# BLE_Master.net
KiCad netlist of a schematic drawn in EAGLE
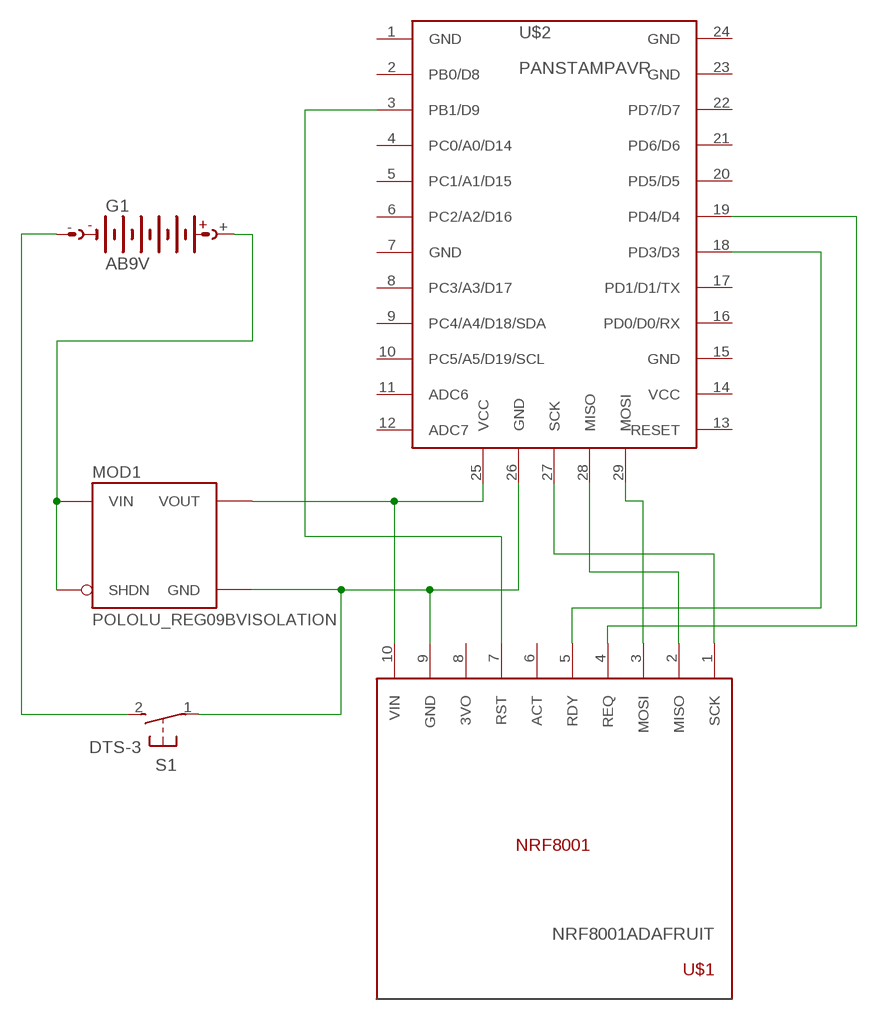
[diagram p0: schematic, sheet 1]

(export (version "E")
  (design (tool "Eeschema 10.0.6"))
  (components
    (comp (ref "G1")
      (value "AB9V")
      (footprint "eagle-import:AB9V")
      (libsource (lib "eagle-import") (part "AB9V"))
    )
    (comp (ref "MOD1")
      (value "POLOLU_REG09BVISOLATION")
      (footprint "eagle-import:POLOLU_REG09B_ISO")
      (libsource (lib "eagle-import") (part "POLOLU_REG09BVISOLATION"))
    )
    (comp (ref "S1")
      (value "DTS-3")
      (footprint "eagle-import:DTS-3")
      (libsource (lib "eagle-import") (part "DTS-3"))
    )
    (comp (ref "U$1")
      (value "NRF8001ADAFRUIT")
      (footprint "eagle-import:NRF8001_ADAFRUIT")
      (libsource (lib "eagle-import") (part "NRF8001ADAFRUIT"))
    )
    (comp (ref "U$2")
      (value "PANSTAMPAVR")
      (footprint "eagle-import:PANSTAMP")
      (libsource (lib "eagle-import") (part "PANSTAMPAVR"))
    )
  )
  (nets
    (net (code "1") (name "Net-(G1-Pad-)") (class "Default")
      (node (ref "G1") (pin "-") (pinfunction "-_-") (pintype "passive"))
      (node (ref "S1") (pin "2") (pinfunction "2_2") (pintype "passive"))
    )
    (net (code "2") (name "Net-(MOD1-GND)") (class "Default")
      (node (ref "MOD1") (pin "G") (pinfunction "GND_G") (pintype "power_in"))
      (node (ref "S1") (pin "1") (pinfunction "1_1") (pintype "passive"))
      (node (ref "U$1") (pin "9") (pinfunction "GND_9") (pintype "bidirectional"))
      (node (ref "U$2") (pin "26") (pinfunction "GND_26") (pintype "bidirectional"))
    )
    (net (code "3") (name "Net-(MOD1-SHDN)") (class "Default")
      (node (ref "G1") (pin "+") (pinfunction "+_+") (pintype "passive"))
      (node (ref "MOD1") (pin "I") (pinfunction "VIN_I") (pintype "power_in"))
      (node (ref "MOD1") (pin "S") (pinfunction "SHDN_S") (pintype "input"))
    )
    (net (code "4") (name "Net-(MOD1-VOUT)") (class "Default")
      (node (ref "MOD1") (pin "O") (pinfunction "VOUT_O") (pintype "output"))
      (node (ref "U$1") (pin "10") (pinfunction "VIN_10") (pintype "bidirectional"))
      (node (ref "U$2") (pin "25") (pinfunction "VCC_25") (pintype "bidirectional"))
    )
    (net (code "5") (name "Net-(U$1-MISO)") (class "Default")
      (node (ref "U$1") (pin "2") (pinfunction "MISO_2") (pintype "bidirectional"))
      (node (ref "U$2") (pin "28") (pinfunction "MISO_28") (pintype "bidirectional"))
    )
    (net (code "6") (name "Net-(U$1-MOSI)") (class "Default")
      (node (ref "U$1") (pin "3") (pinfunction "MOSI_3") (pintype "bidirectional"))
      (node (ref "U$2") (pin "29") (pinfunction "MOSI_29") (pintype "bidirectional"))
    )
    (net (code "7") (name "Net-(U$1-RDY)") (class "Default")
      (node (ref "U$1") (pin "5") (pinfunction "RDY_5") (pintype "bidirectional"))
      (node (ref "U$2") (pin "18") (pinfunction "PD3/D3_18") (pintype "bidirectional"))
    )
    (net (code "8") (name "Net-(U$1-REQ)") (class "Default")
      (node (ref "U$1") (pin "4") (pinfunction "REQ_4") (pintype "bidirectional"))
      (node (ref "U$2") (pin "19") (pinfunction "PD4/D4_19") (pintype "bidirectional"))
    )
    (net (code "9") (name "Net-(U$1-RST)") (class "Default")
      (node (ref "U$1") (pin "7") (pinfunction "RST_7") (pintype "bidirectional"))
      (node (ref "U$2") (pin "3") (pinfunction "PB1/D9_3") (pintype "bidirectional"))
    )
    (net (code "10") (name "Net-(U$1-SCK)") (class "Default")
      (node (ref "U$1") (pin "1") (pinfunction "SCK_1") (pintype "bidirectional"))
      (node (ref "U$2") (pin "27") (pinfunction "SCK_27") (pintype "bidirectional"))
    )
    (net (code "11") (name "unconnected-(U$1-3VO-Pad8)") (class "Default")
      (node (ref "U$1") (pin "8") (pinfunction "3VO_8") (pintype "bidirectional"))
    )
    (net (code "12") (name "unconnected-(U$1-ACT-Pad6)") (class "Default")
      (node (ref "U$1") (pin "6") (pinfunction "ACT_6") (pintype "bidirectional"))
    )
    (net (code "13") (name "unconnected-(U$2-ADC6-Pad11)") (class "Default")
      (node (ref "U$2") (pin "11") (pinfunction "ADC6_11") (pintype "bidirectional"))
    )
    (net (code "14") (name "unconnected-(U$2-ADC7-Pad12)") (class "Default")
      (node (ref "U$2") (pin "12") (pinfunction "ADC7_12") (pintype "bidirectional"))
    )
    (net (code "15") (name "unconnected-(U$2-GND-Pad1)") (class "Default")
      (node (ref "U$2") (pin "1") (pinfunction "GND_1") (pintype "bidirectional"))
    )
    (net (code "16") (name "unconnected-(U$2-GND-Pad7)") (class "Default")
      (node (ref "U$2") (pin "7") (pinfunction "GND_7") (pintype "bidirectional"))
    )
    (net (code "17") (name "unconnected-(U$2-GND-Pad15)") (class "Default")
      (node (ref "U$2") (pin "15") (pinfunction "GND_15") (pintype "bidirectional"))
    )
    (net (code "18") (name "unconnected-(U$2-GND-Pad23)") (class "Default")
      (node (ref "U$2") (pin "23") (pinfunction "GND_23") (pintype "bidirectional"))
    )
    (net (code "19") (name "unconnected-(U$2-GND-Pad24)") (class "Default")
      (node (ref "U$2") (pin "24") (pinfunction "GND_24") (pintype "bidirectional"))
    )
    (net (code "20") (name "unconnected-(U$2-PB0{slash}D8-Pad2)") (class "Default")
      (node (ref "U$2") (pin "2") (pinfunction "PB0/D8_2") (pintype "bidirectional"))
    )
    (net (code "21") (name "unconnected-(U$2-PC0{slash}A0{slash}D14-Pad4)") (class "Default")
      (node (ref "U$2") (pin "4") (pinfunction "PC0/A0/D14_4") (pintype "bidirectional"))
    )
    (net (code "22") (name "unconnected-(U$2-PC1{slash}A1{slash}D15-Pad5)") (class "Default")
      (node (ref "U$2") (pin "5") (pinfunction "PC1/A1/D15_5") (pintype "bidirectional"))
    )
    (net (code "23") (name "unconnected-(U$2-PC2{slash}A2{slash}D16-Pad6)") (class "Default")
      (node (ref "U$2") (pin "6") (pinfunction "PC2/A2/D16_6") (pintype "bidirectional"))
    )
    (net (code "24") (name "unconnected-(U$2-PC3{slash}A3{slash}D17-Pad8)") (class "Default")
      (node (ref "U$2") (pin "8") (pinfunction "PC3/A3/D17_8") (pintype "bidirectional"))
    )
    (net (code "25") (name "unconnected-(U$2-PC4{slash}A4{slash}D18{slash}SDA-Pad9)") (class "Default")
      (node (ref "U$2") (pin "9") (pinfunction "PC4/A4/D18/SDA_9") (pintype "bidirectional"))
    )
    (net (code "26") (name "unconnected-(U$2-PC5{slash}A5{slash}D19{slash}SCL-Pad10)") (class "Default")
      (node (ref "U$2") (pin "10") (pinfunction "PC5/A5/D19/SCL_10") (pintype "bidirectional"))
    )
    (net (code "27") (name "unconnected-(U$2-PD0{slash}D0{slash}RX-Pad16)") (class "Default")
      (node (ref "U$2") (pin "16") (pinfunction "PD0/D0/RX_16") (pintype "bidirectional"))
    )
    (net (code "28") (name "unconnected-(U$2-PD1{slash}D1{slash}TX-Pad17)") (class "Default")
      (node (ref "U$2") (pin "17") (pinfunction "PD1/D1/TX_17") (pintype "bidirectional"))
    )
    (net (code "29") (name "unconnected-(U$2-PD5{slash}D5-Pad20)") (class "Default")
      (node (ref "U$2") (pin "20") (pinfunction "PD5/D5_20") (pintype "bidirectional"))
    )
    (net (code "30") (name "unconnected-(U$2-PD6{slash}D6-Pad21)") (class "Default")
      (node (ref "U$2") (pin "21") (pinfunction "PD6/D6_21") (pintype "bidirectional"))
    )
    (net (code "31") (name "unconnected-(U$2-PD7{slash}D7-Pad22)") (class "Default")
      (node (ref "U$2") (pin "22") (pinfunction "PD7/D7_22") (pintype "bidirectional"))
    )
    (net (code "32") (name "unconnected-(U$2-RESET-Pad13)") (class "Default")
      (node (ref "U$2") (pin "13") (pinfunction "RESET_13") (pintype "bidirectional"))
    )
    (net (code "33") (name "unconnected-(U$2-VCC-Pad14)") (class "Default")
      (node (ref "U$2") (pin "14") (pinfunction "VCC_14") (pintype "bidirectional"))
    )
  )
)
